# Power.net
KiCad netlist of a schematic drawn in Altium Designer
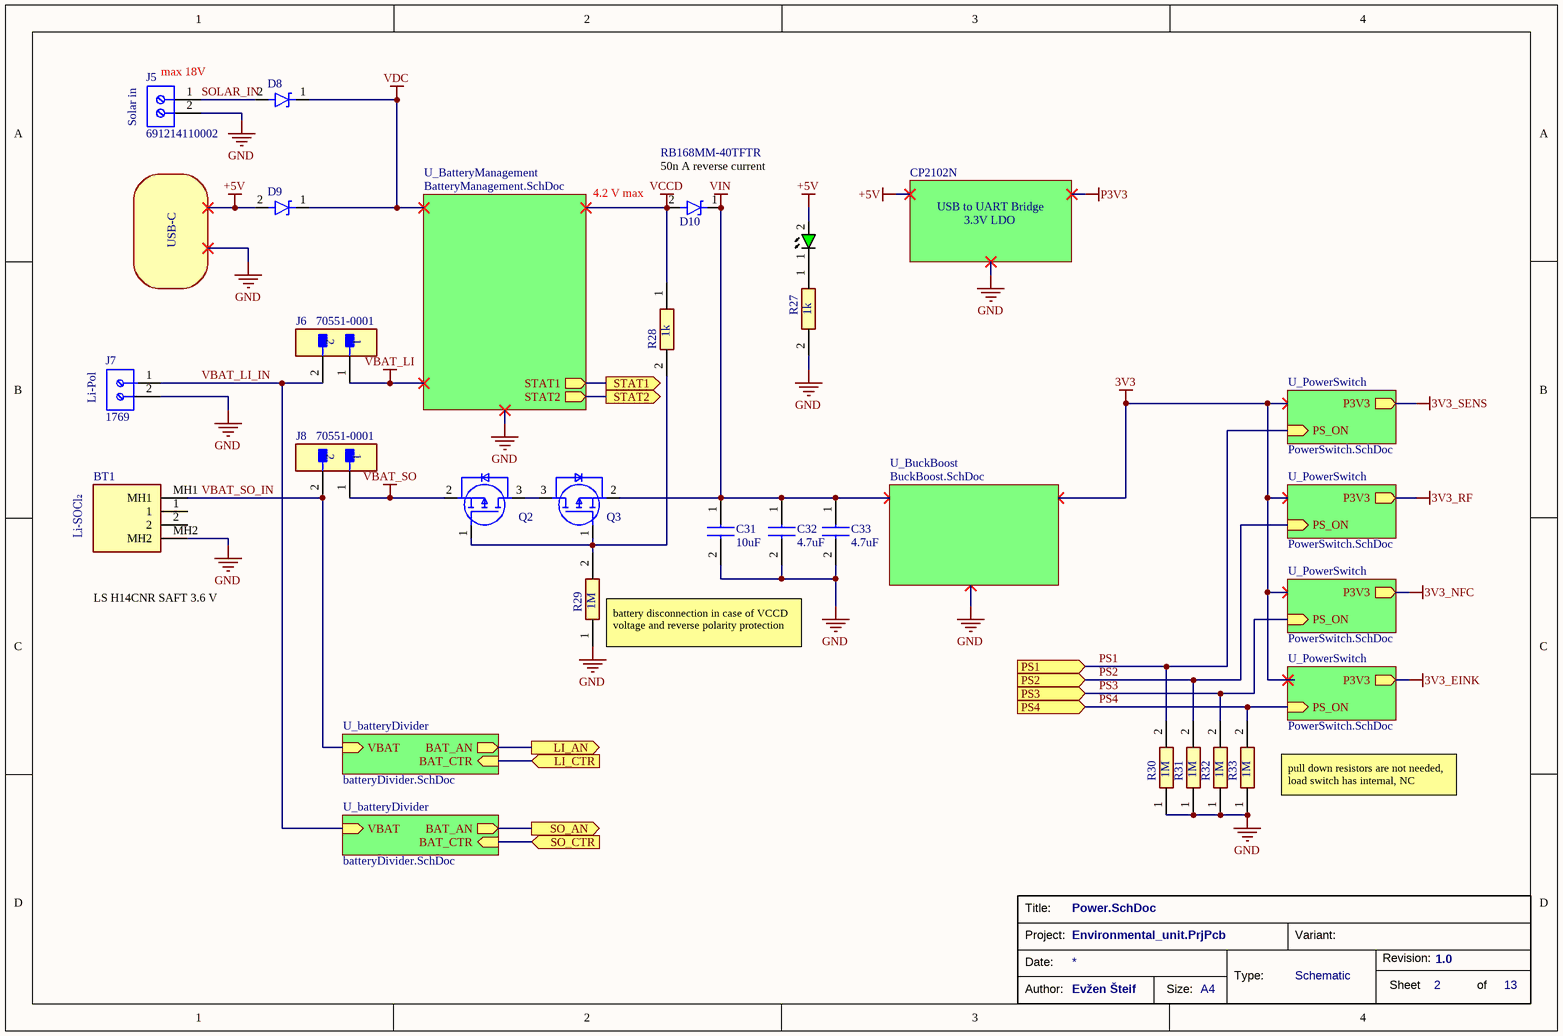
[diagram p0: Power.SchDoc]

(export (version "E")
  (design (tool "Eeschema 10.0.6"))
  (components
    (comp (ref "BT1")
      (value "BX0036")
      (footprint "SamacSys:BX0036")
      (description "Battery")
      (fields (field (name "MOUSER PART NUMBER") "122-BX0036"))
      (libsource (lib "*") (part "BX0036"))
    )
    (comp (ref "C31")
      (value "10uF")
      (footprint "SamacSys:GRM18x")
      (description "Capacitor")
      (fields
        (field (name "MANUFACTURER_PART_NUMBER") "GRM188R61E106KA73D")
        (field (name "MOUSER PART NUMBER") "81-GRM188R61E106KA3D")
      )
      (libsource (lib "*") (part "GRM188R61E106KA73D"))
    )
    (comp (ref "C32")
      (value "4.7uF")
      (footprint "SamacSys:CAPC1608X90N")
      (description "Capacitor")
      (fields
        (field (name "MANUFACTURER_PART_NUMBER") "GRM188R61E475KE11J")
        (field (name "MOUSER PART NUMBER") "81-GRM188R61E475KE1J")
      )
      (libsource (lib "*") (part "GRM188R61E475KE11J"))
    )
    (comp (ref "C33")
      (value "4.7uF")
      (footprint "SamacSys:CAPC1608X90N")
      (description "Capacitor")
      (fields
        (field (name "MANUFACTURER_PART_NUMBER") "GRM188R61E475KE11J")
        (field (name "MOUSER PART NUMBER") "81-GRM188R61E475KE1J")
      )
      (libsource (lib "*") (part "GRM188R61E475KE11J"))
    )
    (comp (ref "D8")
      (value "RB161MM-20TR")
      (footprint "SamacSys:RB161MM20TR")
      (description "Schottky Diode")
      (fields (field (name "MOUSER PART NUMBER") "755-RB161MM-20TR"))
      (libsource (lib "SamacSys") (part "RB161MM-20TR"))
    )
    (comp (ref "D9")
      (value "RB161MM-20TR")
      (footprint "SamacSys:RB161MM20TR")
      (description "Schottky Diode")
      (fields (field (name "MOUSER PART NUMBER") "755-RB161MM-20TR"))
      (libsource (lib "SamacSys") (part "RB161MM-20TR"))
    )
    (comp (ref "D10")
      (value "RB168MM-40TFTR")
      (footprint "SamacSys:RB168MM40TFTR")
      (description "Schottky Diode")
      (fields
        (field (name "MANUFACTURER_PART_NUMBER") "RB168MM-40TFTR")
        (field (name "MOUSER PART NUMBER") "755-RB168MM-40TFTR")
      )
      (libsource (lib "SamacSys") (part "RB168MM-40TFTR"))
    )
    (comp (ref "J5")
      (value "691214110002")
      (footprint "691214110002")
      (fields (field (name "VOLTAGE") "300V"))
      (libsource (lib "Altium Content Vault") (part "TBL - 1R - 02P - Screw"))
    )
    (comp (ref "J6")
      (value "70551-0001")
      (footprint "FP-70551-0036-MFG")
      (description "CONN HEADER R/A 2POS 2.54MM")
      (fields
        (field (name "OCTOPART") "https://octopart.com/70551-0036-molex-773165")
        (field (name "MANUFACTURER") "Molex")
      )
      (libsource (lib "Altium Content Vault") (part "3bc925449376181038e59eaffc5286c"))
    )
    (comp (ref "J7")
      (value "1769")
      (footprint "SamacSys:1769")
      (description "Connector")
      (fields (field (name "MOUSER PART NUMBER") "485-1769"))
      (libsource (lib "SamacSys") (part "1769"))
    )
    (comp (ref "J8")
      (value "70551-0001")
      (footprint "FP-70551-0036-MFG")
      (description "CONN HEADER R/A 2POS 2.54MM")
      (fields
        (field (name "OCTOPART") "https://octopart.com/70551-0036-molex-773165")
        (field (name "MANUFACTURER") "Molex")
      )
      (libsource (lib "Altium Content Vault") (part "3bc925449376181038e59eaffc5286c"))
    )
    (comp (ref "LED6")
      (value "150060GS75000")
      (footprint "SamacSys:LEDC1608X80N")
      (description "LED")
      (fields (field (name "MOUSER PART NUMBER") "710-150060GS75000"))
      (libsource (lib "SamacSys") (part "150060GS75000"))
    )
    (comp (ref "Q2")
      (value "SSM3J358R,LF")
      (footprint "SamacSys:SOTFL95P240X88-3N")
      (description "MOSFET (P-Channel)")
      (fields (field (name "MOUSER PART NUMBER") "757-SSM3J358RLF"))
      (libsource (lib "SamacSys") (part "SSM3J358R,LF"))
    )
    (comp (ref "Q3")
      (value "SSM3J358R,LF")
      (footprint "SamacSys:SOTFL95P240X88-3N")
      (description "MOSFET (P-Channel)")
      (fields (field (name "MOUSER PART NUMBER") "757-SSM3J358RLF"))
      (libsource (lib "SamacSys") (part "SSM3J358R,LF"))
    )
    (comp (ref "R27")
      (value "1k")
      (footprint "SamacSys:RESC1005X35N")
      (description "Resistor")
      (fields
        (field (name "MANUFACTURER_PART_NUMBER") "RT0402FRE071KL")
        (field (name "ARROW PART NUMBER") "RT0402FRE07100KL")
      )
      (libsource (lib "SamacSys") (part "RT0402FRE071KL"))
    )
    (comp (ref "R28")
      (value "1k")
      (footprint "SamacSys:RESC1005X35N")
      (description "Resistor")
      (fields
        (field (name "MANUFACTURER_PART_NUMBER") "RT0402FRE071KL")
        (field (name "ARROW PART NUMBER") "RT0402FRE07100KL")
      )
      (libsource (lib "SamacSys") (part "RT0402FRE071KL"))
    )
    (comp (ref "R29")
      (value "1M")
      (footprint "SamacSys:RESC1005X40N")
      (description "Resistor")
      (fields
        (field (name "MANUFACTURER_PART_NUMBER") "RC0402FR-071ML")
        (field (name "MOUSER PART NUMBER") "603-RC0402FR-071ML")
      )
      (libsource (lib "*") (part "RC0402FR-071ML"))
    )
    (comp (ref "R30")
      (value "1M")
      (footprint "SamacSys:RESC1005X40N")
      (description "Resistor")
      (fields
        (field (name "MANUFACTURER_PART_NUMBER") "RC0402FR-071ML")
        (field (name "MOUSER PART NUMBER") "603-RC0402FR-071ML")
      )
      (libsource (lib "*") (part "RC0402FR-071ML"))
    )
    (comp (ref "R31")
      (value "1M")
      (footprint "SamacSys:RESC1005X40N")
      (description "Resistor")
      (fields
        (field (name "MANUFACTURER_PART_NUMBER") "RC0402FR-071ML")
        (field (name "MOUSER PART NUMBER") "603-RC0402FR-071ML")
      )
      (libsource (lib "*") (part "RC0402FR-071ML"))
    )
    (comp (ref "R32")
      (value "1M")
      (footprint "SamacSys:RESC1005X40N")
      (description "Resistor")
      (fields
        (field (name "MANUFACTURER_PART_NUMBER") "RC0402FR-071ML")
        (field (name "MOUSER PART NUMBER") "603-RC0402FR-071ML")
      )
      (libsource (lib "*") (part "RC0402FR-071ML"))
    )
    (comp (ref "R33")
      (value "1M")
      (footprint "SamacSys:RESC1005X40N")
      (description "Resistor")
      (fields
        (field (name "MANUFACTURER_PART_NUMBER") "RC0402FR-071ML")
        (field (name "MOUSER PART NUMBER") "603-RC0402FR-071ML")
      )
      (libsource (lib "*") (part "RC0402FR-071ML"))
    )
  )
  (nets
    (net (code "1") (name "+5V") (class "Default")
      (node (ref "D9") (pin "2") (pinfunction "A_2") (pintype "passive"))
      (node (ref "LED6") (pin "2") (pinfunction "A_2") (pintype "passive"))
    )
    (net (code "4") (name "/PS1") (class "Default")
      (node (ref "R30") (pin "2") (pinfunction "2_2") (pintype "passive"))
    )
    (net (code "5") (name "/PS2") (class "Default")
      (node (ref "R31") (pin "2") (pinfunction "2_2") (pintype "passive"))
    )
    (net (code "6") (name "/PS3") (class "Default")
      (node (ref "R32") (pin "2") (pinfunction "2_2") (pintype "passive"))
    )
    (net (code "7") (name "/PS4") (class "Default")
      (node (ref "R33") (pin "2") (pinfunction "2_2") (pintype "passive"))
    )
    (net (code "8") (name "/SOLAR_IN") (class "Default")
      (node (ref "D8") (pin "2") (pinfunction "A_2") (pintype "passive"))
      (node (ref "J5") (pin "1") (pinfunction "1_1") (pintype "passive"))
    )
    (net (code "13") (name "/VBAT_LI_IN") (class "Default")
      (node (ref "J6") (pin "2") (pinfunction "2_2") (pintype "passive"))
      (node (ref "J7") (pin "1") (pinfunction "1_1") (pintype "passive"))
    )
    (net (code "14") (name "/VBAT_SO_IN") (class "Default")
      (node (ref "BT1") (pin "MH1") (pinfunction "MH1_MH1") (pintype "passive"))
      (node (ref "J8") (pin "2") (pinfunction "2_2") (pintype "passive"))
    )
    (net (code "20") (name "GND") (class "Default")
      (node (ref "BT1") (pin "MH2") (pinfunction "MH2_MH2") (pintype "passive"))
      (node (ref "C31") (pin "2") (pinfunction "2_2") (pintype "passive"))
      (node (ref "C32") (pin "2") (pinfunction "2_2") (pintype "passive"))
      (node (ref "C33") (pin "2") (pinfunction "2_2") (pintype "passive"))
      (node (ref "J5") (pin "2") (pinfunction "2_2") (pintype "passive"))
      (node (ref "J7") (pin "2") (pinfunction "2_2") (pintype "passive"))
      (node (ref "R27") (pin "2") (pinfunction "2_2") (pintype "passive"))
      (node (ref "R29") (pin "1") (pinfunction "1_1") (pintype "passive"))
      (node (ref "R30") (pin "1") (pinfunction "1_1") (pintype "passive"))
      (node (ref "R31") (pin "1") (pinfunction "1_1") (pintype "passive"))
      (node (ref "R32") (pin "1") (pinfunction "1_1") (pintype "passive"))
      (node (ref "R33") (pin "1") (pinfunction "1_1") (pintype "passive"))
    )
    (net (code "21") (name "Net-(LED6-K)") (class "Default")
      (node (ref "LED6") (pin "1") (pinfunction "K_1") (pintype "passive"))
      (node (ref "R27") (pin "1") (pinfunction "1_1") (pintype "passive"))
    )
    (net (code "22") (name "Net-(Q2-D)") (class "Default")
      (node (ref "Q2") (pin "3") (pinfunction "D_3") (pintype "passive"))
      (node (ref "Q3") (pin "3") (pinfunction "D_3") (pintype "passive"))
    )
    (net (code "23") (name "Net-(Q2-G)") (class "Default")
      (node (ref "Q2") (pin "1") (pinfunction "G_1") (pintype "passive"))
      (node (ref "Q3") (pin "1") (pinfunction "G_1") (pintype "passive"))
      (node (ref "R28") (pin "2") (pinfunction "2_2") (pintype "passive"))
      (node (ref "R29") (pin "2") (pinfunction "2_2") (pintype "passive"))
    )
    (net (code "25") (name "VBAT_LI") (class "Default")
      (node (ref "J6") (pin "1") (pinfunction "1_1") (pintype "passive"))
    )
    (net (code "26") (name "VBAT_SO") (class "Default")
      (node (ref "J8") (pin "1") (pinfunction "1_1") (pintype "passive"))
      (node (ref "Q2") (pin "2") (pinfunction "S_2") (pintype "passive"))
    )
    (net (code "27") (name "VCCD") (class "Default")
      (node (ref "D10") (pin "2") (pinfunction "A_2") (pintype "passive"))
      (node (ref "R28") (pin "1") (pinfunction "1_1") (pintype "passive"))
    )
    (net (code "28") (name "VDC") (class "Default")
      (node (ref "D8") (pin "1") (pinfunction "K_1") (pintype "passive"))
      (node (ref "D9") (pin "1") (pinfunction "K_1") (pintype "passive"))
    )
    (net (code "29") (name "VIN") (class "Default")
      (node (ref "C31") (pin "1") (pinfunction "1_1") (pintype "passive"))
      (node (ref "C32") (pin "1") (pinfunction "1_1") (pintype "passive"))
      (node (ref "C33") (pin "1") (pinfunction "1_1") (pintype "passive"))
      (node (ref "D10") (pin "1") (pinfunction "K_1") (pintype "passive"))
      (node (ref "Q3") (pin "2") (pinfunction "S_2") (pintype "passive"))
    )
    (net (code "30") (name "unconnected-(BT1-Pad1)") (class "Default")
      (node (ref "BT1") (pin "1") (pinfunction "1_1") (pintype "passive"))
    )
    (net (code "31") (name "unconnected-(BT1-Pad2)") (class "Default")
      (node (ref "BT1") (pin "2") (pinfunction "2_2") (pintype "passive"))
    )
  )
)
